# C64_ROM_Selector_-_ATMega368.net
KiCad netlist of a schematic drawn in EAGLE
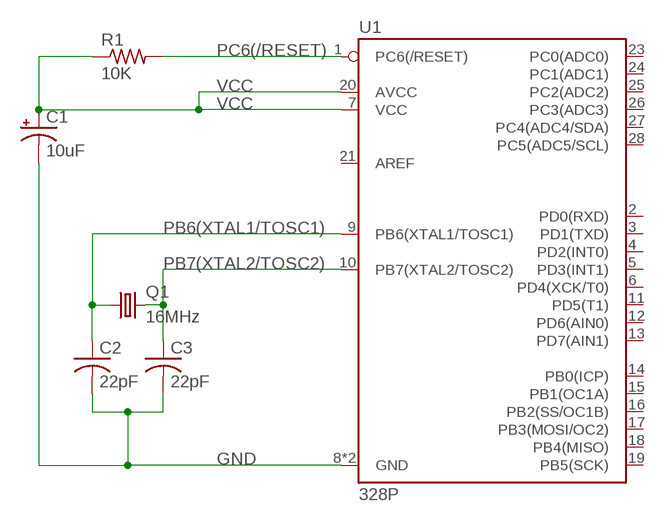
[diagram p0: schematic, sheet 1]

(export (version "E")
  (design (tool "Eeschema 10.0.6"))
  (components
    (comp (ref "C1")
      (value "10uF")
      (footprint "eagle-import:E1,8-4")
      (libsource (lib "eagle-import") (part "CPOL-USE1.8-4"))
    )
    (comp (ref "C2")
      (value "22pF")
      (footprint "eagle-import:C025-024X044")
      (libsource (lib "eagle-import") (part "C-US025-024X044"))
    )
    (comp (ref "C3")
      (value "22pF")
      (footprint "eagle-import:C025-024X044")
      (libsource (lib "eagle-import") (part "C-US025-024X044"))
    )
    (comp (ref "Q1")
      (value "16MHz")
      (footprint "eagle-import:HC49_S")
      (libsource (lib "eagle-import") (part "CRYSTALHC49S"))
    )
    (comp (ref "R1")
      (value "10K")
      (footprint "eagle-import:0207_10")
      (libsource (lib "eagle-import") (part "R-US_0207/10"))
    )
    (comp (ref "U1")
      (value "328P")
      (footprint "eagle-import:DIP28")
      (libsource (lib "eagle-import") (part "ATMEGA328P_PDIP"))
    )
  )
  (nets
    (net (code "1") (name "/GND") (class "Default")
      (node (ref "C1") (pin "-") (pinfunction "-_-") (pintype "passive"))
      (node (ref "C2") (pin "2") (pinfunction "2_2") (pintype "passive"))
      (node (ref "C3") (pin "2") (pinfunction "2_2") (pintype "passive"))
      (node (ref "U1") (pin "22") (pinfunction "GND_22") (pintype "bidirectional"))
      (node (ref "U1") (pin "8") (pinfunction "GND_8") (pintype "bidirectional"))
    )
    (net (code "2") (name "/PB6(XTAL1{slash}TOSC1)") (class "Default")
      (node (ref "C2") (pin "1") (pinfunction "1_1") (pintype "passive"))
      (node (ref "Q1") (pin "1") (pinfunction "1_1") (pintype "passive"))
      (node (ref "U1") (pin "9") (pinfunction "PB6(XTAL1/TOSC1)_9") (pintype "bidirectional"))
    )
    (net (code "3") (name "/PB7(XTAL2{slash}TOSC2)") (class "Default")
      (node (ref "C3") (pin "1") (pinfunction "1_1") (pintype "passive"))
      (node (ref "Q1") (pin "2") (pinfunction "2_2") (pintype "passive"))
      (node (ref "U1") (pin "10") (pinfunction "PB7(XTAL2/TOSC2)_10") (pintype "bidirectional"))
    )
    (net (code "4") (name "/PC6({slash}RESET)") (class "Default")
      (node (ref "R1") (pin "2") (pinfunction "2_2") (pintype "passive"))
      (node (ref "U1") (pin "1") (pinfunction "PC6(/RESET)_1") (pintype "bidirectional"))
    )
    (net (code "5") (name "/VCC") (class "Default")
      (node (ref "C1") (pin "+") (pinfunction "+_+") (pintype "passive"))
      (node (ref "R1") (pin "1") (pinfunction "1_1") (pintype "passive"))
      (node (ref "U1") (pin "20") (pinfunction "AVCC_20") (pintype "bidirectional"))
      (node (ref "U1") (pin "7") (pinfunction "VCC_7") (pintype "bidirectional"))
    )
    (net (code "6") (name "unconnected-(U1-AREF-Pad21)") (class "Default")
      (node (ref "U1") (pin "21") (pinfunction "AREF_21") (pintype "bidirectional"))
    )
    (net (code "7") (name "unconnected-(U1-PB0(ICP)-Pad14)") (class "Default")
      (node (ref "U1") (pin "14") (pinfunction "PB0(ICP)_14") (pintype "bidirectional"))
    )
    (net (code "8") (name "unconnected-(U1-PB1(OC1A)-Pad15)") (class "Default")
      (node (ref "U1") (pin "15") (pinfunction "PB1(OC1A)_15") (pintype "bidirectional"))
    )
    (net (code "9") (name "unconnected-(U1-PB2(SS{slash}OC1B)-Pad16)") (class "Default")
      (node (ref "U1") (pin "16") (pinfunction "PB2(SS/OC1B)_16") (pintype "bidirectional"))
    )
    (net (code "10") (name "unconnected-(U1-PB3(MOSI{slash}OC2)-Pad17)") (class "Default")
      (node (ref "U1") (pin "17") (pinfunction "PB3(MOSI/OC2)_17") (pintype "bidirectional"))
    )
    (net (code "11") (name "unconnected-(U1-PB4(MISO)-Pad18)") (class "Default")
      (node (ref "U1") (pin "18") (pinfunction "PB4(MISO)_18") (pintype "bidirectional"))
    )
    (net (code "12") (name "unconnected-(U1-PB5(SCK)-Pad19)") (class "Default")
      (node (ref "U1") (pin "19") (pinfunction "PB5(SCK)_19") (pintype "bidirectional"))
    )
    (net (code "13") (name "unconnected-(U1-PC0(ADC0)-Pad23)") (class "Default")
      (node (ref "U1") (pin "23") (pinfunction "PC0(ADC0)_23") (pintype "bidirectional"))
    )
    (net (code "14") (name "unconnected-(U1-PC1(ADC1)-Pad24)") (class "Default")
      (node (ref "U1") (pin "24") (pinfunction "PC1(ADC1)_24") (pintype "bidirectional"))
    )
    (net (code "15") (name "unconnected-(U1-PC2(ADC2)-Pad25)") (class "Default")
      (node (ref "U1") (pin "25") (pinfunction "PC2(ADC2)_25") (pintype "bidirectional"))
    )
    (net (code "16") (name "unconnected-(U1-PC3(ADC3)-Pad26)") (class "Default")
      (node (ref "U1") (pin "26") (pinfunction "PC3(ADC3)_26") (pintype "bidirectional"))
    )
    (net (code "17") (name "unconnected-(U1-PC4(ADC4{slash}SDA)-Pad27)") (class "Default")
      (node (ref "U1") (pin "27") (pinfunction "PC4(ADC4/SDA)_27") (pintype "bidirectional"))
    )
    (net (code "18") (name "unconnected-(U1-PC5(ADC5{slash}SCL)-Pad28)") (class "Default")
      (node (ref "U1") (pin "28") (pinfunction "PC5(ADC5/SCL)_28") (pintype "bidirectional"))
    )
    (net (code "19") (name "unconnected-(U1-PD0(RXD)-Pad2)") (class "Default")
      (node (ref "U1") (pin "2") (pinfunction "PD0(RXD)_2") (pintype "bidirectional"))
    )
    (net (code "20") (name "unconnected-(U1-PD1(TXD)-Pad3)") (class "Default")
      (node (ref "U1") (pin "3") (pinfunction "PD1(TXD)_3") (pintype "bidirectional"))
    )
    (net (code "21") (name "unconnected-(U1-PD2(INT0)-Pad4)") (class "Default")
      (node (ref "U1") (pin "4") (pinfunction "PD2(INT0)_4") (pintype "bidirectional"))
    )
    (net (code "22") (name "unconnected-(U1-PD3(INT1)-Pad5)") (class "Default")
      (node (ref "U1") (pin "5") (pinfunction "PD3(INT1)_5") (pintype "bidirectional"))
    )
    (net (code "23") (name "unconnected-(U1-PD4(XCK{slash}T0)-Pad6)") (class "Default")
      (node (ref "U1") (pin "6") (pinfunction "PD4(XCK/T0)_6") (pintype "bidirectional"))
    )
    (net (code "24") (name "unconnected-(U1-PD5(T1)-Pad11)") (class "Default")
      (node (ref "U1") (pin "11") (pinfunction "PD5(T1)_11") (pintype "bidirectional"))
    )
    (net (code "25") (name "unconnected-(U1-PD6(AIN0)-Pad12)") (class "Default")
      (node (ref "U1") (pin "12") (pinfunction "PD6(AIN0)_12") (pintype "bidirectional"))
    )
    (net (code "26") (name "unconnected-(U1-PD7(AIN1)-Pad13)") (class "Default")
      (node (ref "U1") (pin "13") (pinfunction "PD7(AIN1)_13") (pintype "bidirectional"))
    )
  )
)
